# MotoDriver.net
KiCad netlist of a schematic drawn in Altium Designer
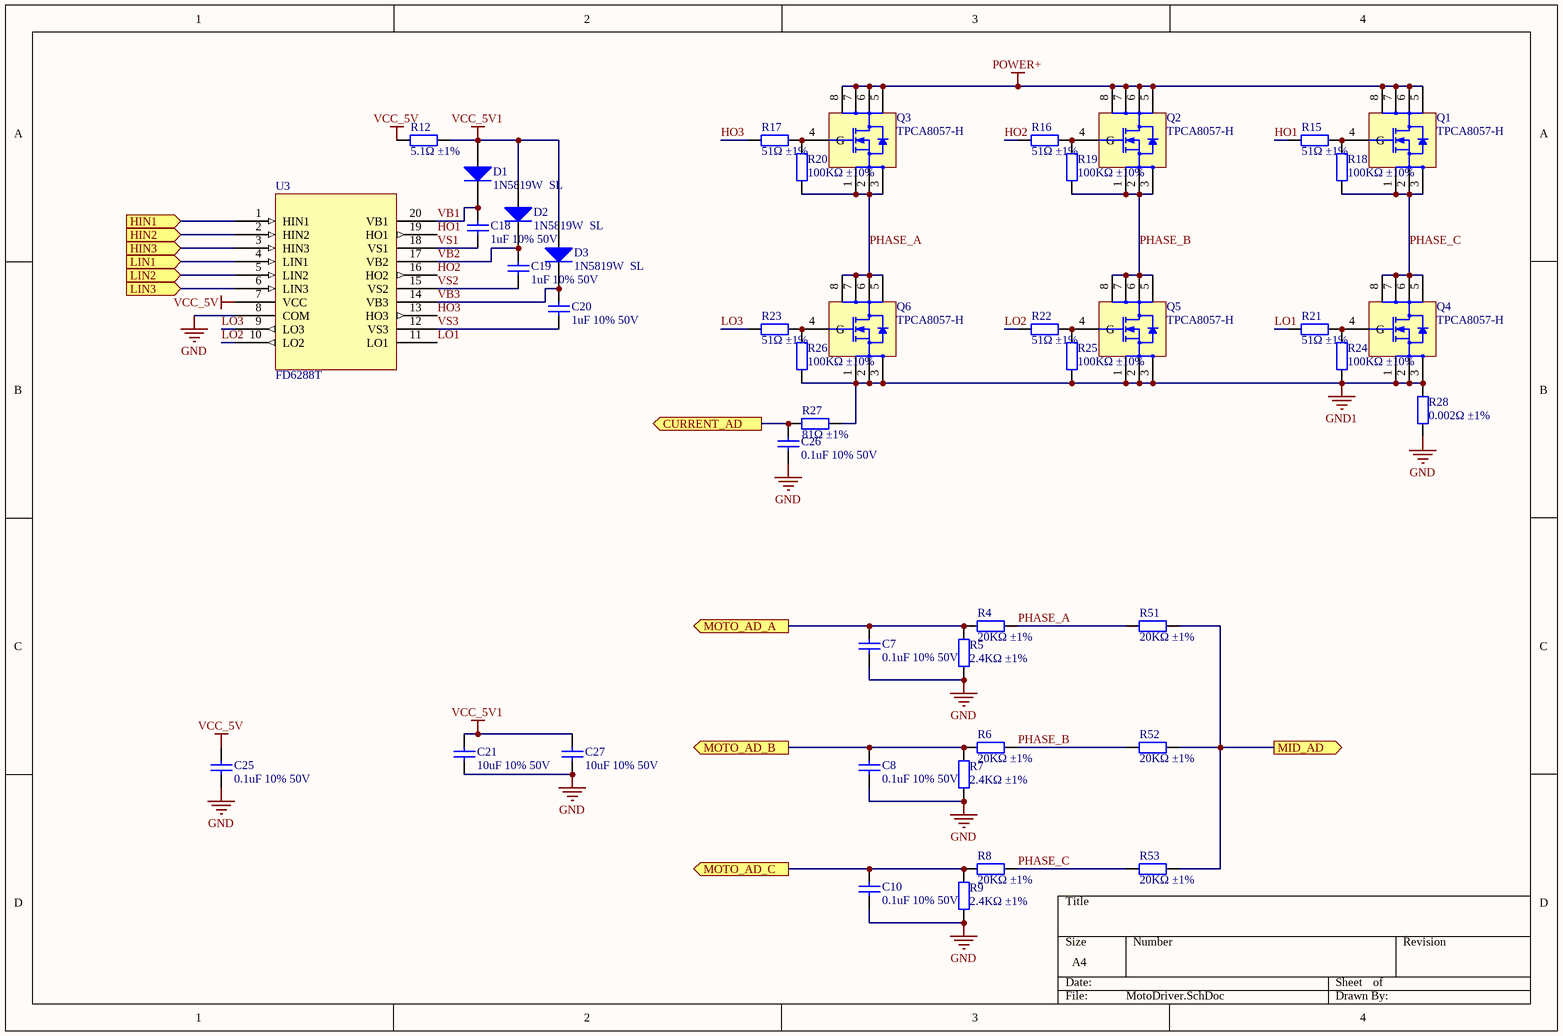
[diagram p0: MotoDriver.SchDoc]

(export (version "E")
  (design (tool "Eeschema 10.0.6"))
  (components
    (comp (ref "C7")
      (value "0.1uF 10% 50V")
      (footprint "0603_C")
      (description "贴片电容")
      (libsource (lib "Cap") (part "0603 4.7uF (475) 10% 16V"))
    )
    (comp (ref "C8")
      (value "0.1uF 10% 50V")
      (footprint "0603_C")
      (description "贴片电容")
      (libsource (lib "Cap") (part "0603 4.7uF (475) 10% 16V"))
    )
    (comp (ref "C10")
      (value "0.1uF 10% 50V")
      (footprint "0603_C")
      (description "贴片电容")
      (libsource (lib "Cap") (part "0603 4.7uF (475) 10% 16V"))
    )
    (comp (ref "C18")
      (value "1uF 10% 50V")
      (footprint "0805_C")
      (description "贴片电容")
      (libsource (lib "Cap") (part "0805 1uF (105) 10% 50V"))
    )
    (comp (ref "C19")
      (value "1uF 10% 50V")
      (footprint "0805_C")
      (description "贴片电容")
      (libsource (lib "Cap") (part "0805 1uF (105) 10% 50V"))
    )
    (comp (ref "C20")
      (value "1uF 10% 50V")
      (footprint "0805_C")
      (description "贴片电容")
      (libsource (lib "Cap") (part "0805 1uF (105) 10% 50V"))
    )
    (comp (ref "C21")
      (value "10uF 10% 50V")
      (footprint "0805_C")
      (description "贴片电容")
      (libsource (lib "Cap") (part "0805 1uF (105) 10% 50V"))
    )
    (comp (ref "C25")
      (value "0.1uF 10% 50V")
      (footprint "0603_C")
      (description "贴片电容")
      (libsource (lib "Cap") (part "0603 4.7uF (475) 10% 16V"))
    )
    (comp (ref "C26")
      (value "0.1uF 10% 50V")
      (footprint "0603_C")
      (description "贴片电容")
      (libsource (lib "Cap") (part "0603 4.7uF (475) 10% 16V"))
    )
    (comp (ref "C27")
      (value "10uF 10% 50V")
      (footprint "0805_C")
      (description "贴片电容")
      (libsource (lib "Cap") (part "0603 4.7uF (475) 10% 16V"))
    )
    (comp (ref "D1")
      (value "1N5819W  SL")
      (footprint "SOD-123")
      (description "肖特基二极管")
      (libsource (lib "Diode") (part "SOD-123 B5819W  SL"))
    )
    (comp (ref "D2")
      (value "1N5819W  SL")
      (footprint "SOD-123")
      (description "肖特基二极管")
      (libsource (lib "Diode") (part "SOD-123 B5819W  SL"))
    )
    (comp (ref "D3")
      (value "1N5819W  SL")
      (footprint "SOD-123")
      (description "肖特基二极管")
      (libsource (lib "Diode") (part "SOD-123 B5819W  SL"))
    )
    (comp (ref "Q1")
      (value "TPCA8057-H")
      (footprint "TPCA8057-H")
      (description "MOSFETsSilicon N-Channel MOS (U-MOS-H)")
      (libsource (lib "贴片") (part "TPCA8057-H"))
    )
    (comp (ref "Q2")
      (value "TPCA8057-H")
      (footprint "TPCA8057-H")
      (description "MOSFETsSilicon N-Channel MOS (U-MOS-H)")
      (libsource (lib "贴片") (part "TPCA8057-H"))
    )
    (comp (ref "Q3")
      (value "TPCA8057-H")
      (footprint "TPCA8057-H")
      (description "MOSFETsSilicon N-Channel MOS (U-MOS-H)")
      (libsource (lib "贴片") (part "TPCA8057-H"))
    )
    (comp (ref "Q4")
      (value "TPCA8057-H")
      (footprint "TPCA8057-H")
      (description "MOSFETsSilicon N-Channel MOS (U-MOS-H)")
      (libsource (lib "贴片") (part "TPCA8057-H"))
    )
    (comp (ref "Q5")
      (value "TPCA8057-H")
      (footprint "TPCA8057-H")
      (description "MOSFETsSilicon N-Channel MOS (U-MOS-H)")
      (libsource (lib "贴片") (part "TPCA8057-H"))
    )
    (comp (ref "Q6")
      (value "TPCA8057-H")
      (footprint "TPCA8057-H")
      (description "MOSFETsSilicon N-Channel MOS (U-MOS-H)")
      (libsource (lib "贴片") (part "TPCA8057-H"))
    )
    (comp (ref "R4")
      (value "20KΩ ±1%")
      (footprint "0603_R")
      (description "贴片电阻")
      (libsource (lib "RES") (part "0603 2.2Ω (2R20) 1%"))
    )
    (comp (ref "R5")
      (value "2.4KΩ ±1%")
      (footprint "0603_R")
      (description "贴片电阻")
      (libsource (lib "") (part "0603 2.2Ω (2R20) 1%_1"))
    )
    (comp (ref "R6")
      (value "20KΩ ±1%")
      (footprint "0603_R")
      (description "贴片电阻")
      (libsource (lib "RES") (part "0603 2.2Ω (2R20) 1%"))
    )
    (comp (ref "R7")
      (value "2.4KΩ ±1%")
      (footprint "0603_R")
      (description "贴片电阻")
      (libsource (lib "") (part "0603 2.2Ω (2R20) 1%_1"))
    )
    (comp (ref "R8")
      (value "20KΩ ±1%")
      (footprint "0603_R")
      (description "贴片电阻")
      (libsource (lib "RES") (part "0603 2.2Ω (2R20) 1%"))
    )
    (comp (ref "R9")
      (value "2.4KΩ ±1%")
      (footprint "0603_R")
      (description "贴片电阻")
      (libsource (lib "") (part "0603 2.2Ω (2R20) 1%_1"))
    )
    (comp (ref "R12")
      (value "5.1Ω ±1%")
      (footprint "1206_R")
      (description "贴片电阻")
      (libsource (lib "RES") (part "0402 51Ω (51R0) 1%"))
    )
    (comp (ref "R15")
      (value "51Ω ±1%")
      (footprint "0603_R")
      (description "贴片电阻")
      (libsource (lib "RES") (part "0603 2.2Ω (2R20) 1%"))
    )
    (comp (ref "R16")
      (value "51Ω ±1%")
      (footprint "0603_R")
      (description "贴片电阻")
      (libsource (lib "RES") (part "0603 2.2Ω (2R20) 1%"))
    )
    (comp (ref "R17")
      (value "51Ω ±1%")
      (footprint "0603_R")
      (description "贴片电阻")
      (libsource (lib "RES") (part "0603 2.2Ω (2R20) 1%"))
    )
    (comp (ref "R18")
      (value "100KΩ ±10%")
      (footprint "0603_R")
      (description "贴片电阻")
      (libsource (lib "") (part "0603 2.2Ω (2R20) 1%_1"))
    )
    (comp (ref "R19")
      (value "100KΩ ±10%")
      (footprint "0603_R")
      (description "贴片电阻")
      (libsource (lib "") (part "0603 2.2Ω (2R20) 1%_1"))
    )
    (comp (ref "R20")
      (value "100KΩ ±10%")
      (footprint "0603_R")
      (description "贴片电阻")
      (libsource (lib "") (part "0603 2.2Ω (2R20) 1%_1"))
    )
    (comp (ref "R21")
      (value "51Ω ±1%")
      (footprint "0603_R")
      (description "贴片电阻")
      (libsource (lib "RES") (part "0603 2.2Ω (2R20) 1%"))
    )
    (comp (ref "R22")
      (value "51Ω ±1%")
      (footprint "0603_R")
      (description "贴片电阻")
      (libsource (lib "RES") (part "0603 2.2Ω (2R20) 1%"))
    )
    (comp (ref "R23")
      (value "51Ω ±1%")
      (footprint "0603_R")
      (description "贴片电阻")
      (libsource (lib "RES") (part "0603 2.2Ω (2R20) 1%"))
    )
    (comp (ref "R24")
      (value "100KΩ ±10%")
      (footprint "0603_R")
      (description "贴片电阻")
      (libsource (lib "") (part "0603 2.2Ω (2R20) 1%_1"))
    )
    (comp (ref "R25")
      (value "100KΩ ±10%")
      (footprint "0603_R")
      (description "贴片电阻")
      (libsource (lib "") (part "0603 2.2Ω (2R20) 1%_1"))
    )
    (comp (ref "R26")
      (value "100KΩ ±10%")
      (footprint "0603_R")
      (description "贴片电阻")
      (libsource (lib "") (part "0603 2.2Ω (2R20) 1%_1"))
    )
    (comp (ref "R27")
      (value "81Ω ±1%")
      (footprint "0603_R")
      (description "贴片电阻")
      (libsource (lib "RES") (part "0603 2.2Ω (2R20) 1%"))
    )
    (comp (ref "R28")
      (value "0.002Ω ±1%")
      (footprint "RESC2512(6432)_M")
      (description "贴片电阻")
      (libsource (lib "") (part "0603 2.2Ω (2R20) 1%_1"))
    )
    (comp (ref "R51")
      (value "20KΩ ±1%")
      (footprint "0603_R")
      (description "贴片电阻")
      (libsource (lib "RES") (part "0603 2.2Ω (2R20) 1%"))
    )
    (comp (ref "R52")
      (value "20KΩ ±1%")
      (footprint "0603_R")
      (description "贴片电阻")
      (libsource (lib "RES") (part "0603 2.2Ω (2R20) 1%"))
    )
    (comp (ref "R53")
      (value "20KΩ ±1%")
      (footprint "0603_R")
      (description "贴片电阻")
      (libsource (lib "RES") (part "0603 2.2Ω (2R20) 1%"))
    )
    (comp (ref "U3")
      (value "FD6288T")
      (footprint "TSSOP20_M")
      (description "USB to TTL Serial / UART")
      (libsource (lib "贴片") (part "FD6288T"))
    )
  )
  (nets
    (net (code "1") (name "/CURRENT_AD") (class "Default")
      (node (ref "C26") (pin "2") (pinfunction "2_2") (pintype "passive"))
      (node (ref "R27") (pin "1") (pinfunction "1_1") (pintype "passive"))
    )
    (net (code "2") (name "/HIN1") (class "Default")
      (node (ref "U3") (pin "1") (pinfunction "HIN1_1") (pintype "input"))
    )
    (net (code "3") (name "/HIN2") (class "Default")
      (node (ref "U3") (pin "2") (pinfunction "HIN2_2") (pintype "input"))
    )
    (net (code "4") (name "/HIN3") (class "Default")
      (node (ref "U3") (pin "3") (pinfunction "HIN3_3") (pintype "input"))
    )
    (net (code "5") (name "/HO1") (class "Default")
      (node (ref "R15") (pin "1") (pinfunction "1_1") (pintype "passive"))
      (node (ref "U3") (pin "19") (pinfunction "HO1_19") (pintype "output"))
    )
    (net (code "6") (name "/HO2") (class "Default")
      (node (ref "R16") (pin "1") (pinfunction "1_1") (pintype "passive"))
      (node (ref "U3") (pin "16") (pinfunction "HO2_16") (pintype "output"))
    )
    (net (code "7") (name "/HO3") (class "Default")
      (node (ref "R17") (pin "1") (pinfunction "1_1") (pintype "passive"))
      (node (ref "U3") (pin "13") (pinfunction "HO3_13") (pintype "output"))
    )
    (net (code "8") (name "/LIN1") (class "Default")
      (node (ref "U3") (pin "4") (pinfunction "LIN1_4") (pintype "input"))
    )
    (net (code "9") (name "/LIN2") (class "Default")
      (node (ref "U3") (pin "5") (pinfunction "LIN2_5") (pintype "input"))
    )
    (net (code "10") (name "/LIN3") (class "Default")
      (node (ref "U3") (pin "6") (pinfunction "LIN3_6") (pintype "input"))
    )
    (net (code "11") (name "/LO1") (class "Default")
      (node (ref "R21") (pin "1") (pinfunction "1_1") (pintype "passive"))
      (node (ref "U3") (pin "11") (pinfunction "LO1_11") (pintype "open_collector"))
    )
    (net (code "12") (name "/LO2") (class "Default")
      (node (ref "R22") (pin "1") (pinfunction "1_1") (pintype "passive"))
      (node (ref "U3") (pin "10") (pinfunction "LO2_10") (pintype "output"))
    )
    (net (code "13") (name "/LO3") (class "Default")
      (node (ref "R23") (pin "1") (pinfunction "1_1") (pintype "passive"))
      (node (ref "U3") (pin "9") (pinfunction "LO3_9") (pintype "output"))
    )
    (net (code "14") (name "/MID_AD") (class "Default")
      (node (ref "R51") (pin "2") (pinfunction "2_2") (pintype "passive"))
      (node (ref "R52") (pin "2") (pinfunction "2_2") (pintype "passive"))
      (node (ref "R53") (pin "2") (pinfunction "2_2") (pintype "passive"))
    )
    (net (code "15") (name "/MOTO_AD_A") (class "Default")
      (node (ref "C7") (pin "2") (pinfunction "2_2") (pintype "passive"))
      (node (ref "R4") (pin "1") (pinfunction "1_1") (pintype "passive"))
      (node (ref "R5") (pin "2") (pinfunction "2_2") (pintype "passive"))
    )
    (net (code "16") (name "/MOTO_AD_B") (class "Default")
      (node (ref "C8") (pin "2") (pinfunction "2_2") (pintype "passive"))
      (node (ref "R6") (pin "1") (pinfunction "1_1") (pintype "passive"))
      (node (ref "R7") (pin "2") (pinfunction "2_2") (pintype "passive"))
    )
    (net (code "17") (name "/MOTO_AD_C") (class "Default")
      (node (ref "C10") (pin "2") (pinfunction "2_2") (pintype "passive"))
      (node (ref "R8") (pin "1") (pinfunction "1_1") (pintype "passive"))
      (node (ref "R9") (pin "2") (pinfunction "2_2") (pintype "passive"))
    )
    (net (code "18") (name "/PHASE_A") (class "Default")
      (node (ref "Q3") (pin "1") (pinfunction "S_1") (pintype "passive"))
      (node (ref "Q3") (pin "2") (pinfunction "S_2") (pintype "passive"))
      (node (ref "Q3") (pin "3") (pinfunction "S_3") (pintype "passive"))
      (node (ref "Q6") (pin "5") (pinfunction "D_5") (pintype "power_in"))
      (node (ref "Q6") (pin "6") (pinfunction "D_6") (pintype "power_in"))
      (node (ref "Q6") (pin "7") (pinfunction "D_7") (pintype "power_in"))
      (node (ref "Q6") (pin "8") (pinfunction "D_8") (pintype "power_in"))
      (node (ref "R20") (pin "1") (pinfunction "1_1") (pintype "passive"))
      (node (ref "R4") (pin "2") (pinfunction "2_2") (pintype "passive"))
      (node (ref "R51") (pin "1") (pinfunction "1_1") (pintype "passive"))
    )
    (net (code "19") (name "/PHASE_B") (class "Default")
      (node (ref "Q2") (pin "1") (pinfunction "S_1") (pintype "passive"))
      (node (ref "Q2") (pin "2") (pinfunction "S_2") (pintype "passive"))
      (node (ref "Q2") (pin "3") (pinfunction "S_3") (pintype "passive"))
      (node (ref "Q5") (pin "5") (pinfunction "D_5") (pintype "power_in"))
      (node (ref "Q5") (pin "6") (pinfunction "D_6") (pintype "power_in"))
      (node (ref "Q5") (pin "7") (pinfunction "D_7") (pintype "power_in"))
      (node (ref "Q5") (pin "8") (pinfunction "D_8") (pintype "power_in"))
      (node (ref "R19") (pin "1") (pinfunction "1_1") (pintype "passive"))
      (node (ref "R52") (pin "1") (pinfunction "1_1") (pintype "passive"))
      (node (ref "R6") (pin "2") (pinfunction "2_2") (pintype "passive"))
    )
    (net (code "20") (name "/PHASE_C") (class "Default")
      (node (ref "Q1") (pin "1") (pinfunction "S_1") (pintype "passive"))
      (node (ref "Q1") (pin "2") (pinfunction "S_2") (pintype "passive"))
      (node (ref "Q1") (pin "3") (pinfunction "S_3") (pintype "passive"))
      (node (ref "Q4") (pin "5") (pinfunction "D_5") (pintype "power_in"))
      (node (ref "Q4") (pin "6") (pinfunction "D_6") (pintype "power_in"))
      (node (ref "Q4") (pin "7") (pinfunction "D_7") (pintype "power_in"))
      (node (ref "Q4") (pin "8") (pinfunction "D_8") (pintype "power_in"))
      (node (ref "R18") (pin "1") (pinfunction "1_1") (pintype "passive"))
      (node (ref "R53") (pin "1") (pinfunction "1_1") (pintype "passive"))
      (node (ref "R8") (pin "2") (pinfunction "2_2") (pintype "passive"))
    )
    (net (code "21") (name "/VB1") (class "Default")
      (node (ref "C18") (pin "2") (pinfunction "2_2") (pintype "passive"))
      (node (ref "D1") (pin "2") (pinfunction "K_2") (pintype "passive"))
      (node (ref "U3") (pin "20") (pinfunction "VB1_20") (pintype "passive"))
    )
    (net (code "22") (name "/VB2") (class "Default")
      (node (ref "C19") (pin "2") (pinfunction "2_2") (pintype "passive"))
      (node (ref "D2") (pin "2") (pinfunction "K_2") (pintype "passive"))
      (node (ref "U3") (pin "17") (pinfunction "VB2_17") (pintype "passive"))
    )
    (net (code "23") (name "/VB3") (class "Default")
      (node (ref "C20") (pin "2") (pinfunction "2_2") (pintype "passive"))
      (node (ref "D3") (pin "2") (pinfunction "K_2") (pintype "passive"))
      (node (ref "U3") (pin "14") (pinfunction "VB3_14") (pintype "passive"))
    )
    (net (code "24") (name "/VS1") (class "Default")
      (node (ref "C18") (pin "1") (pinfunction "1_1") (pintype "passive"))
      (node (ref "U3") (pin "18") (pinfunction "VS1_18") (pintype "passive"))
    )
    (net (code "25") (name "/VS2") (class "Default")
      (node (ref "C19") (pin "1") (pinfunction "1_1") (pintype "passive"))
      (node (ref "U3") (pin "15") (pinfunction "VS2_15") (pintype "passive"))
    )
    (net (code "26") (name "/VS3") (class "Default")
      (node (ref "C20") (pin "1") (pinfunction "1_1") (pintype "passive"))
      (node (ref "U3") (pin "12") (pinfunction "VS3_12") (pintype "passive"))
    )
    (net (code "27") (name "GND") (class "Default")
      (node (ref "C10") (pin "1") (pinfunction "1_1") (pintype "passive"))
      (node (ref "C21") (pin "1") (pinfunction "1_1") (pintype "passive"))
      (node (ref "C25") (pin "1") (pinfunction "1_1") (pintype "passive"))
      (node (ref "C26") (pin "1") (pinfunction "1_1") (pintype "passive"))
      (node (ref "C27") (pin "1") (pinfunction "1_1") (pintype "passive"))
      (node (ref "C7") (pin "1") (pinfunction "1_1") (pintype "passive"))
      (node (ref "C8") (pin "1") (pinfunction "1_1") (pintype "passive"))
      (node (ref "R28") (pin "1") (pinfunction "1_1") (pintype "passive"))
      (node (ref "R5") (pin "1") (pinfunction "1_1") (pintype "passive"))
      (node (ref "R7") (pin "1") (pinfunction "1_1") (pintype "passive"))
      (node (ref "R9") (pin "1") (pinfunction "1_1") (pintype "passive"))
      (node (ref "U3") (pin "8") (pinfunction "COM_8") (pintype "passive"))
    )
    (net (code "28") (name "GND1") (class "Default")
      (node (ref "Q4") (pin "1") (pinfunction "S_1") (pintype "passive"))
      (node (ref "Q4") (pin "2") (pinfunction "S_2") (pintype "passive"))
      (node (ref "Q4") (pin "3") (pinfunction "S_3") (pintype "passive"))
      (node (ref "Q5") (pin "1") (pinfunction "S_1") (pintype "passive"))
      (node (ref "Q5") (pin "2") (pinfunction "S_2") (pintype "passive"))
      (node (ref "Q5") (pin "3") (pinfunction "S_3") (pintype "passive"))
      (node (ref "Q6") (pin "1") (pinfunction "S_1") (pintype "passive"))
      (node (ref "Q6") (pin "2") (pinfunction "S_2") (pintype "passive"))
      (node (ref "Q6") (pin "3") (pinfunction "S_3") (pintype "passive"))
      (node (ref "R24") (pin "1") (pinfunction "1_1") (pintype "passive"))
      (node (ref "R25") (pin "1") (pinfunction "1_1") (pintype "passive"))
      (node (ref "R26") (pin "1") (pinfunction "1_1") (pintype "passive"))
      (node (ref "R27") (pin "2") (pinfunction "2_2") (pintype "passive"))
      (node (ref "R28") (pin "2") (pinfunction "2_2") (pintype "passive"))
    )
    (net (code "29") (name "Net-(Q1-G)") (class "Default")
      (node (ref "Q1") (pin "4") (pinfunction "G_4") (pintype "passive"))
      (node (ref "R15") (pin "2") (pinfunction "2_2") (pintype "passive"))
      (node (ref "R18") (pin "2") (pinfunction "2_2") (pintype "passive"))
    )
    (net (code "30") (name "Net-(Q2-G)") (class "Default")
      (node (ref "Q2") (pin "4") (pinfunction "G_4") (pintype "passive"))
      (node (ref "R16") (pin "2") (pinfunction "2_2") (pintype "passive"))
      (node (ref "R19") (pin "2") (pinfunction "2_2") (pintype "passive"))
    )
    (net (code "31") (name "Net-(Q3-G)") (class "Default")
      (node (ref "Q3") (pin "4") (pinfunction "G_4") (pintype "passive"))
      (node (ref "R17") (pin "2") (pinfunction "2_2") (pintype "passive"))
      (node (ref "R20") (pin "2") (pinfunction "2_2") (pintype "passive"))
    )
    (net (code "32") (name "Net-(Q4-G)") (class "Default")
      (node (ref "Q4") (pin "4") (pinfunction "G_4") (pintype "passive"))
      (node (ref "R21") (pin "2") (pinfunction "2_2") (pintype "passive"))
      (node (ref "R24") (pin "2") (pinfunction "2_2") (pintype "passive"))
    )
    (net (code "33") (name "Net-(Q5-G)") (class "Default")
      (node (ref "Q5") (pin "4") (pinfunction "G_4") (pintype "passive"))
      (node (ref "R22") (pin "2") (pinfunction "2_2") (pintype "passive"))
      (node (ref "R25") (pin "2") (pinfunction "2_2") (pintype "passive"))
    )
    (net (code "34") (name "Net-(Q6-G)") (class "Default")
      (node (ref "Q6") (pin "4") (pinfunction "G_4") (pintype "passive"))
      (node (ref "R23") (pin "2") (pinfunction "2_2") (pintype "passive"))
      (node (ref "R26") (pin "2") (pinfunction "2_2") (pintype "passive"))
    )
    (net (code "35") (name "POWER+") (class "Default")
      (node (ref "Q1") (pin "5") (pinfunction "D_5") (pintype "power_in"))
      (node (ref "Q1") (pin "6") (pinfunction "D_6") (pintype "power_in"))
      (node (ref "Q1") (pin "7") (pinfunction "D_7") (pintype "power_in"))
      (node (ref "Q1") (pin "8") (pinfunction "D_8") (pintype "power_in"))
      (node (ref "Q2") (pin "5") (pinfunction "D_5") (pintype "power_in"))
      (node (ref "Q2") (pin "6") (pinfunction "D_6") (pintype "power_in"))
      (node (ref "Q2") (pin "7") (pinfunction "D_7") (pintype "power_in"))
      (node (ref "Q2") (pin "8") (pinfunction "D_8") (pintype "power_in"))
      (node (ref "Q3") (pin "5") (pinfunction "D_5") (pintype "power_in"))
      (node (ref "Q3") (pin "6") (pinfunction "D_6") (pintype "power_in"))
      (node (ref "Q3") (pin "7") (pinfunction "D_7") (pintype "power_in"))
      (node (ref "Q3") (pin "8") (pinfunction "D_8") (pintype "power_in"))
    )
    (net (code "36") (name "VCC_5V") (class "Default")
      (node (ref "C25") (pin "2") (pinfunction "2_2") (pintype "passive"))
      (node (ref "R12") (pin "1") (pinfunction "1_1") (pintype "passive"))
      (node (ref "U3") (pin "7") (pinfunction "VCC_7") (pintype "power_in"))
    )
    (net (code "37") (name "VCC_5V1") (class "Default")
      (node (ref "C21") (pin "2") (pinfunction "2_2") (pintype "passive"))
      (node (ref "C27") (pin "2") (pinfunction "2_2") (pintype "passive"))
      (node (ref "D1") (pin "1") (pinfunction "A_1") (pintype "passive"))
      (node (ref "D2") (pin "1") (pinfunction "A_1") (pintype "passive"))
      (node (ref "D3") (pin "1") (pinfunction "A_1") (pintype "passive"))
      (node (ref "R12") (pin "2") (pinfunction "2_2") (pintype "passive"))
    )
  )
)
